# type-C.net
KiCad netlist of a schematic drawn in Altium Designer
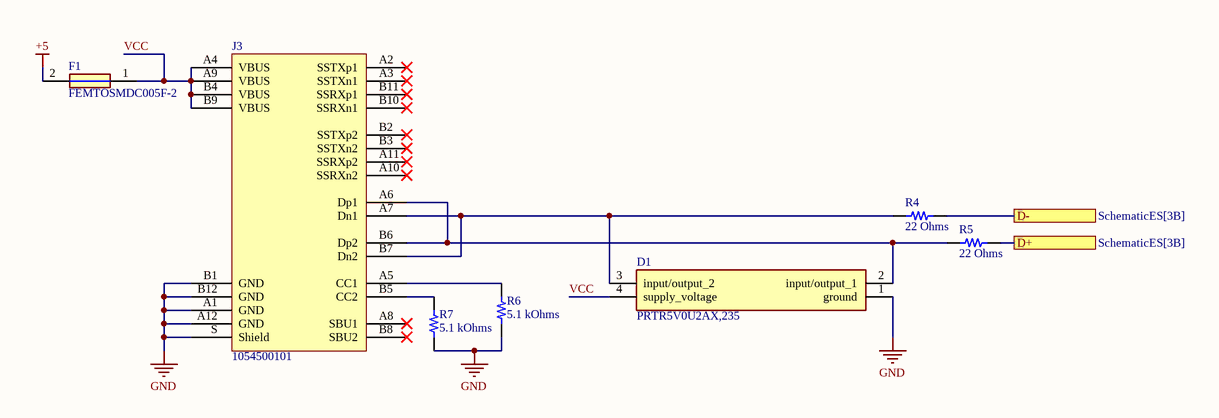
[diagram p0: type-C.SchDoc]

(export (version "E")
  (design (tool "Eeschema 10.0.6"))
  (components
    (comp (ref "D1")
      (value "PRTR5V0U2AX,235")
      (footprint "SamacSys:PRTR5V0U2X")
      (description "Diode")
      (fields (field (name "MOUSER PART NUMBER") "771-PRTR5V0U2AX,235"))
      (libsource (lib "*") (part "PRTR5V0U2AX,235"))
    )
    (comp (ref "F1")
      (value "FEMTOSMDC005F-2")
      (footprint "SamacSys:FUSC1608X85N")
      (description "Fuse")
      (fields (field (name "MOUSER PART NUMBER") "650-FEMTOSMDC005F-2"))
      (libsource (lib "paiload1") (part "FEMTOSMDC005F-2"))
    )
    (comp (ref "J3")
      (value "1054500101")
      (footprint "Molex 1054500101")
      (description "CONN RCP USB3.1 TYPEC 24P SMD RA")
      (fields (field (name "MANUFACTURER") "Molex"))
      (libsource (lib "Celestial Altium Library - altium_library") (part "USB 3.0 Type C"))
    )
    (comp (ref "R4")
      (value "22 Ohms")
      (footprint "RES 0805_2012")
      (description "RES 22 OHM 5% 1/2W 0805")
      (fields
        (field (name "PART NUMBER") "RPC0805JT22R0-UP")
        (field (name "MANUFACTURER") "Stackpole Electronics Inc")
      )
      (libsource (lib "Celestial Altium Library - altium_library") (part "Resistor"))
    )
    (comp (ref "R5")
      (value "22 Ohms")
      (footprint "RES 0805_2012")
      (description "RES 22 OHM 5% 1/2W 0805")
      (fields
        (field (name "PART NUMBER") "RPC0805JT22R0-UP")
        (field (name "MANUFACTURER") "Stackpole Electronics Inc")
      )
      (libsource (lib "Celestial Altium Library - altium_library") (part "Resistor"))
    )
    (comp (ref "R6")
      (value "5.1 kOhms")
      (footprint "RES 0805_2012")
      (description "RES 5.1K OHM 0.1% 1/8W 0805")
      (fields (field (name "PART NUMBER") "TNPW08055K10BEEA") (field (name "MANUFACTURER") "Vishay Dale"))
      (libsource (lib "Celestial Altium Library - altium_library") (part "Resistor"))
    )
    (comp (ref "R7")
      (value "5.1 kOhms")
      (footprint "RES 0805_2012")
      (description "RES 5.1K OHM 0.1% 1/8W 0805")
      (fields (field (name "PART NUMBER") "TNPW08055K10BEEA") (field (name "MANUFACTURER") "Vishay Dale"))
      (libsource (lib "Celestial Altium Library - altium_library") (part "Resistor"))
    )
  )
  (nets
    (net (code "1") (name "+5") (class "Default")
      (node (ref "F1") (pin "2") (pinfunction "2_2") (pintype "passive"))
    )
    (net (code "2") (name "/D+") (class "Default")
      (node (ref "R5") (pin "2") (pinfunction "2_2") (pintype "passive"))
    )
    (net (code "3") (name "/D-") (class "Default")
      (node (ref "R4") (pin "2") (pinfunction "2_2") (pintype "passive"))
    )
    (net (code "4") (name "/VCC") (class "Default")
      (node (ref "D1") (pin "4") (pinfunction "supply_voltage_4") (pintype "passive"))
      (node (ref "F1") (pin "1") (pinfunction "1_1") (pintype "passive"))
      (node (ref "J3") (pin "A4") (pinfunction "VBUS_A4") (pintype "passive"))
      (node (ref "J3") (pin "A9") (pinfunction "VBUS_A9") (pintype "passive"))
      (node (ref "J3") (pin "B4") (pinfunction "VBUS_B4") (pintype "passive"))
      (node (ref "J3") (pin "B9") (pinfunction "VBUS_B9") (pintype "passive"))
    )
    (net (code "5") (name "GND") (class "Default")
      (node (ref "D1") (pin "1") (pinfunction "ground_1") (pintype "passive"))
      (node (ref "J3") (pin "A1") (pinfunction "GND_A1") (pintype "passive"))
      (node (ref "J3") (pin "A12") (pinfunction "GND_A12") (pintype "passive"))
      (node (ref "J3") (pin "B1") (pinfunction "GND_B1") (pintype "passive"))
      (node (ref "J3") (pin "B12") (pinfunction "GND_B12") (pintype "passive"))
      (node (ref "J3") (pin "S") (pinfunction "Shield_S") (pintype "passive"))
      (node (ref "R6") (pin "2") (pinfunction "2_2") (pintype "passive"))
      (node (ref "R7") (pin "2") (pinfunction "2_2") (pintype "passive"))
    )
    (net (code "6") (name "Net-(D1-input{slash}output_1)") (class "Default")
      (node (ref "D1") (pin "2") (pinfunction "input/output_1_2") (pintype "passive"))
      (node (ref "J3") (pin "A6") (pinfunction "Dp1_A6") (pintype "passive"))
      (node (ref "J3") (pin "B6") (pinfunction "Dp2_B6") (pintype "passive"))
      (node (ref "R5") (pin "1") (pinfunction "1_1") (pintype "passive"))
    )
    (net (code "7") (name "Net-(D1-input{slash}output_2)") (class "Default")
      (node (ref "D1") (pin "3") (pinfunction "input/output_2_3") (pintype "passive"))
      (node (ref "J3") (pin "A7") (pinfunction "Dn1_A7") (pintype "passive"))
      (node (ref "J3") (pin "B7") (pinfunction "Dn2_B7") (pintype "passive"))
      (node (ref "R4") (pin "1") (pinfunction "1_1") (pintype "passive"))
    )
    (net (code "8") (name "Net-(J3-CC1)") (class "Default")
      (node (ref "J3") (pin "A5") (pinfunction "CC1_A5") (pintype "passive"))
      (node (ref "R6") (pin "1") (pinfunction "1_1") (pintype "passive"))
    )
    (net (code "9") (name "Net-(J3-CC2)") (class "Default")
      (node (ref "J3") (pin "B5") (pinfunction "CC2_B5") (pintype "passive"))
      (node (ref "R7") (pin "1") (pinfunction "1_1") (pintype "passive"))
    )
    (net (code "10") (name "unconnected-(J3-SBU1-PadA8)") (class "Default")
      (node (ref "J3") (pin "A8") (pinfunction "SBU1_A8") (pintype "passive+no_connect"))
    )
    (net (code "11") (name "unconnected-(J3-SBU2-PadB8)") (class "Default")
      (node (ref "J3") (pin "B8") (pinfunction "SBU2_B8") (pintype "passive+no_connect"))
    )
    (net (code "12") (name "unconnected-(J3-SSRXn1-PadB10)") (class "Default")
      (node (ref "J3") (pin "B10") (pinfunction "SSRXn1_B10") (pintype "passive+no_connect"))
    )
    (net (code "13") (name "unconnected-(J3-SSRXn2-PadA10)") (class "Default")
      (node (ref "J3") (pin "A10") (pinfunction "SSRXn2_A10") (pintype "passive+no_connect"))
    )
    (net (code "14") (name "unconnected-(J3-SSRXp1-PadB11)") (class "Default")
      (node (ref "J3") (pin "B11") (pinfunction "SSRXp1_B11") (pintype "passive+no_connect"))
    )
    (net (code "15") (name "unconnected-(J3-SSRXp2-PadA11)") (class "Default")
      (node (ref "J3") (pin "A11") (pinfunction "SSRXp2_A11") (pintype "passive+no_connect"))
    )
    (net (code "16") (name "unconnected-(J3-SSTXn1-PadA3)") (class "Default")
      (node (ref "J3") (pin "A3") (pinfunction "SSTXn1_A3") (pintype "passive+no_connect"))
    )
    (net (code "17") (name "unconnected-(J3-SSTXn2-PadB3)") (class "Default")
      (node (ref "J3") (pin "B3") (pinfunction "SSTXn2_B3") (pintype "passive+no_connect"))
    )
    (net (code "18") (name "unconnected-(J3-SSTXp1-PadA2)") (class "Default")
      (node (ref "J3") (pin "A2") (pinfunction "SSTXp1_A2") (pintype "passive+no_connect"))
    )
    (net (code "19") (name "unconnected-(J3-SSTXp2-PadB2)") (class "Default")
      (node (ref "J3") (pin "B2") (pinfunction "SSTXp2_B2") (pintype "passive+no_connect"))
    )
  )
)
